# imu.net
KiCad netlist of a schematic drawn in EAGLE
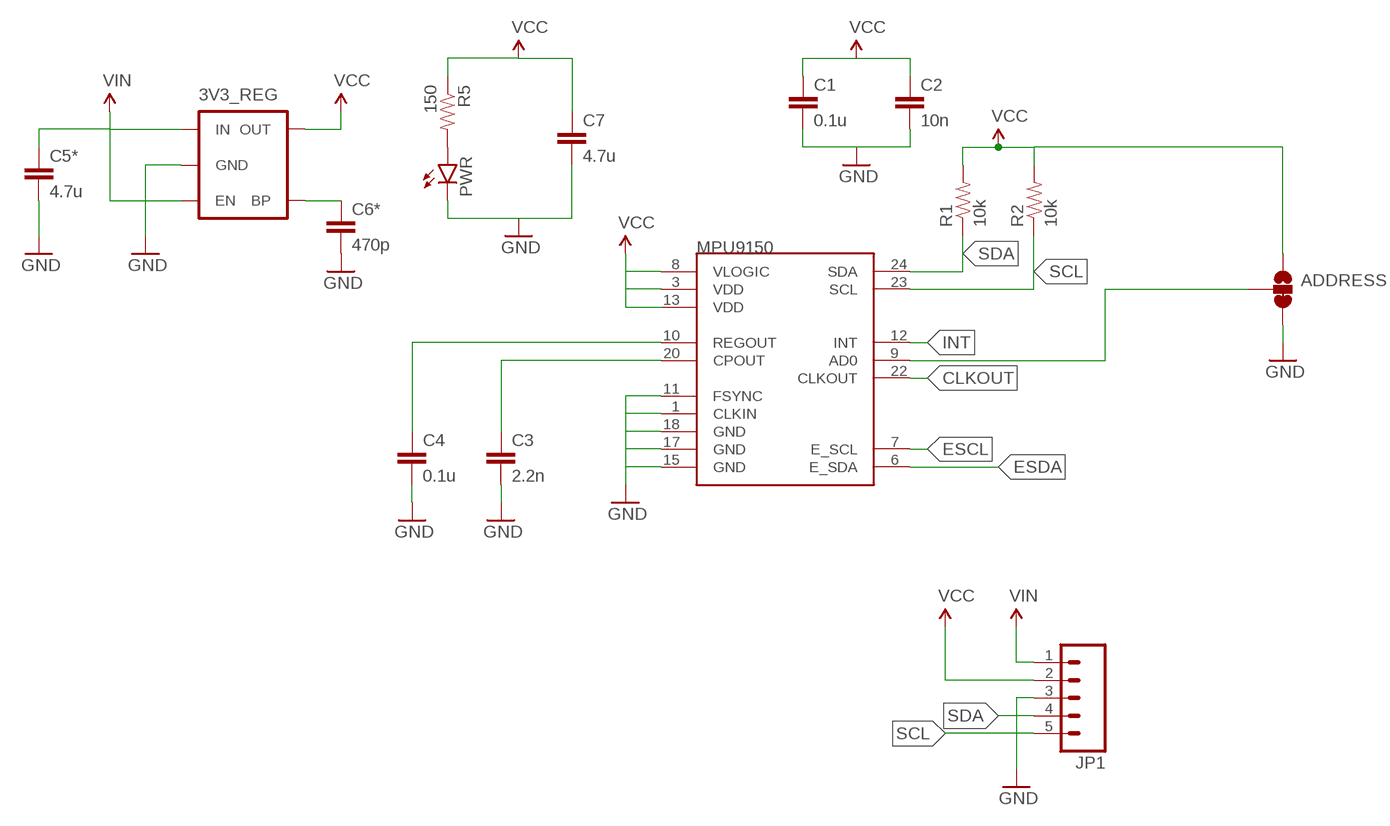
[diagram p0: schematic, sheet 1]

(export (version "E")
  (design (tool "Eeschema 10.0.6"))
  (components
    (comp (ref "3V3_REG")
      (value "MIC52053.3V")
      (footprint "eagle-import:SOT23-5")
      (libsource (lib "eagle-import") (part "MIC52053.3V"))
    )
    (comp (ref "ADDRESS")
      (value "JUMPER-PAD-3-2OF3_NC_BY_TRACE_SMALL")
      (footprint "eagle-import:PAD-JUMPER-3-2OF3_NC_BY_TRACE_YES_SILK_FULL_BOX")
      (libsource (lib "eagle-import") (part "JUMPER-PAD-3-2OF3_NC_BY_TRACE_SMALL"))
    )
    (comp (ref "C1")
      (value "0.1u")
      (footprint "eagle-import:0805")
      (libsource (lib "eagle-import") (part "CAP0805"))
    )
    (comp (ref "C2")
      (value "10n")
      (footprint "eagle-import:0805")
      (libsource (lib "eagle-import") (part "CAP0805"))
    )
    (comp (ref "C3")
      (value "2.2n")
      (footprint "eagle-import:0805")
      (libsource (lib "eagle-import") (part "CAP0805"))
    )
    (comp (ref "C4")
      (value "0.1u")
      (footprint "eagle-import:0805")
      (libsource (lib "eagle-import") (part "CAP0805"))
    )
    (comp (ref "C5*")
      (value "4.7u")
      (footprint "eagle-import:0805")
      (libsource (lib "eagle-import") (part "CAP0805"))
    )
    (comp (ref "C6*")
      (value "470p")
      (footprint "eagle-import:0805")
      (libsource (lib "eagle-import") (part "CAP0805"))
    )
    (comp (ref "C7")
      (value "4.7u")
      (footprint "eagle-import:0805")
      (libsource (lib "eagle-import") (part "CAP0805"))
    )
    (comp (ref "JP1")
      (value "M05SMD2")
      (footprint "eagle-import:1X05-1MM-RA")
      (libsource (lib "eagle-import") (part "M05SMD2"))
    )
    (comp (ref "MPU9150")
      (value "MPU-9150QFN-24-NP")
      (footprint "eagle-import:QFN-24-NP")
      (libsource (lib "eagle-import") (part "MPU-9150QFN-24-NP"))
    )
    (comp (ref "PWR")
      (value "LED0805")
      (footprint "eagle-import:LED-0805")
      (libsource (lib "eagle-import") (part "LED0805"))
    )
    (comp (ref "R1")
      (value "10k")
      (footprint "eagle-import:0805")
      (libsource (lib "eagle-import") (part "RESISTOR0805-RES"))
    )
    (comp (ref "R2")
      (value "10k")
      (footprint "eagle-import:0805")
      (libsource (lib "eagle-import") (part "RESISTOR0805-RES"))
    )
    (comp (ref "R5")
      (value "150")
      (footprint "eagle-import:0805")
      (libsource (lib "eagle-import") (part "RESISTOR0805-RES"))
    )
  )
  (nets
    (net (code "1") (name "CLKOUT") (class "Default")
      (node (ref "MPU9150") (pin "22") (pinfunction "CLKOUT_22") (pintype "bidirectional"))
    )
    (net (code "2") (name "ESCL") (class "Default")
      (node (ref "MPU9150") (pin "7") (pinfunction "E_SCL_7") (pintype "bidirectional"))
    )
    (net (code "3") (name "ESDA") (class "Default")
      (node (ref "MPU9150") (pin "6") (pinfunction "E_SDA_6") (pintype "bidirectional"))
    )
    (net (code "4") (name "GND") (class "Default")
      (node (ref "3V3_REG") (pin "2") (pinfunction "GND_2") (pintype "input"))
      (node (ref "ADDRESS") (pin "3") (pinfunction "3_3") (pintype "passive"))
      (node (ref "C1") (pin "2") (pinfunction "2_2") (pintype "passive"))
      (node (ref "C2") (pin "2") (pinfunction "2_2") (pintype "passive"))
      (node (ref "C3") (pin "2") (pinfunction "2_2") (pintype "passive"))
      (node (ref "C4") (pin "2") (pinfunction "2_2") (pintype "passive"))
      (node (ref "C5*") (pin "2") (pinfunction "2_2") (pintype "passive"))
      (node (ref "C6*") (pin "2") (pinfunction "2_2") (pintype "passive"))
      (node (ref "C7") (pin "2") (pinfunction "2_2") (pintype "passive"))
      (node (ref "JP1") (pin "3") (pinfunction "3_3") (pintype "passive"))
      (node (ref "MPU9150") (pin "1") (pinfunction "CLKIN_1") (pintype "bidirectional"))
      (node (ref "MPU9150") (pin "11") (pinfunction "FSYNC_11") (pintype "bidirectional"))
      (node (ref "MPU9150") (pin "15") (pinfunction "GND_15") (pintype "bidirectional"))
      (node (ref "MPU9150") (pin "17") (pinfunction "GND_17") (pintype "bidirectional"))
      (node (ref "MPU9150") (pin "18") (pinfunction "GND_18") (pintype "bidirectional"))
      (node (ref "PWR") (pin "CATHODE") (pinfunction "C_CATHODE") (pintype "passive"))
    )
    (net (code "5") (name "INT") (class "Default")
      (node (ref "MPU9150") (pin "12") (pinfunction "INT_12") (pintype "bidirectional"))
    )
    (net (code "6") (name "Net-(3V3_REG-BP)") (class "Default")
      (node (ref "3V3_REG") (pin "4") (pinfunction "BP_4") (pintype "input"))
      (node (ref "C6*") (pin "1") (pinfunction "1_1") (pintype "passive"))
    )
    (net (code "7") (name "Net-(MPU9150-AD0)") (class "Default")
      (node (ref "ADDRESS") (pin "2") (pinfunction "2_2") (pintype "passive"))
      (node (ref "MPU9150") (pin "9") (pinfunction "AD0_9") (pintype "bidirectional"))
    )
    (net (code "8") (name "Net-(MPU9150-CPOUT)") (class "Default")
      (node (ref "C3") (pin "1") (pinfunction "1_1") (pintype "passive"))
      (node (ref "MPU9150") (pin "20") (pinfunction "CPOUT_20") (pintype "bidirectional"))
    )
    (net (code "9") (name "Net-(MPU9150-REGOUT)") (class "Default")
      (node (ref "C4") (pin "1") (pinfunction "1_1") (pintype "passive"))
      (node (ref "MPU9150") (pin "10") (pinfunction "REGOUT_10") (pintype "bidirectional"))
    )
    (net (code "10") (name "Net-(PWR-A)") (class "Default")
      (node (ref "PWR") (pin "ANODE") (pinfunction "A_ANODE") (pintype "passive"))
      (node (ref "R5") (pin "2") (pinfunction "2_2") (pintype "passive"))
    )
    (net (code "11") (name "SCL") (class "Default")
      (node (ref "JP1") (pin "5") (pinfunction "5_5") (pintype "passive"))
      (node (ref "MPU9150") (pin "23") (pinfunction "SCL_23") (pintype "bidirectional"))
      (node (ref "R2") (pin "1") (pinfunction "1_1") (pintype "passive"))
    )
    (net (code "12") (name "SDA") (class "Default")
      (node (ref "JP1") (pin "4") (pinfunction "4_4") (pintype "passive"))
      (node (ref "MPU9150") (pin "24") (pinfunction "SDA_24") (pintype "bidirectional"))
      (node (ref "R1") (pin "1") (pinfunction "1_1") (pintype "passive"))
    )
    (net (code "13") (name "VCC") (class "Default")
      (node (ref "3V3_REG") (pin "5") (pinfunction "OUT_5") (pintype "passive"))
      (node (ref "ADDRESS") (pin "1") (pinfunction "1_1") (pintype "passive"))
      (node (ref "C1") (pin "1") (pinfunction "1_1") (pintype "passive"))
      (node (ref "C2") (pin "1") (pinfunction "1_1") (pintype "passive"))
      (node (ref "C7") (pin "1") (pinfunction "1_1") (pintype "passive"))
      (node (ref "JP1") (pin "2") (pinfunction "2_2") (pintype "passive"))
      (node (ref "MPU9150") (pin "13") (pinfunction "VDD_13") (pintype "bidirectional"))
      (node (ref "MPU9150") (pin "3") (pinfunction "VDD_3") (pintype "bidirectional"))
      (node (ref "MPU9150") (pin "8") (pinfunction "VLOGIC_8") (pintype "bidirectional"))
      (node (ref "R1") (pin "2") (pinfunction "2_2") (pintype "passive"))
      (node (ref "R2") (pin "2") (pinfunction "2_2") (pintype "passive"))
      (node (ref "R5") (pin "1") (pinfunction "1_1") (pintype "passive"))
    )
    (net (code "14") (name "VIN") (class "Default")
      (node (ref "3V3_REG") (pin "1") (pinfunction "IN_1") (pintype "input"))
      (node (ref "3V3_REG") (pin "3") (pinfunction "EN_3") (pintype "input"))
      (node (ref "C5*") (pin "1") (pinfunction "1_1") (pintype "passive"))
      (node (ref "JP1") (pin "1") (pinfunction "1_1") (pintype "passive"))
    )
  )
)
